# Display_LED.net
KiCad netlist of a schematic drawn in Altium Designer
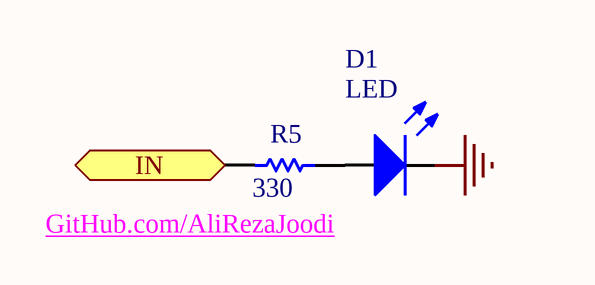
[diagram p0: Display_LED.SchDoc]

(export (version "E")
  (design (tool "Eeschema 10.0.6"))
  (components
    (comp (ref "D1")
      (value "D1")
      (footprint "LED-5mm_Red")
      (description "Typical INFRARED GaAs LED")
      (fields
        (field (name "MANUFACTURER") "Generic Components")
        (field (name "CLASS II") "LED")
        (field (name "PUBLISHER") "Altium Limited")
      )
      (libsource (lib "Miscellaneous Devices") (part "LED"))
    )
    (comp (ref "R5")
      (value "R5")
      (footprint "AXIAL-0.4")
      (description "Resistor")
      (fields
        (field (name "MANUFACTURER") "Generic Components")
        (field (name "ALTIUM_VALUE") "330")
        (field (name "PUBLISHER") "Altium Limited")
      )
      (libsource (lib "Miscellaneous Devices") (part "Res1"))
    )
  )
  (nets
    (net (code "1") (name "/IN") (class "Default")
      (node (ref "R5") (pin "2") (pinfunction "2_2") (pintype "passive"))
    )
    (net (code "2") (name "GND") (class "Default")
      (node (ref "D1") (pin "2") (pinfunction "K_2") (pintype "passive"))
    )
    (net (code "3") (name "Net-(D1-A)") (class "Default")
      (node (ref "D1") (pin "1") (pinfunction "A_1") (pintype "passive"))
      (node (ref "R5") (pin "1") (pinfunction "1_1") (pintype "passive"))
    )
  )
)
